# power_supply.net
KiCad netlist of a schematic drawn in Altium Designer
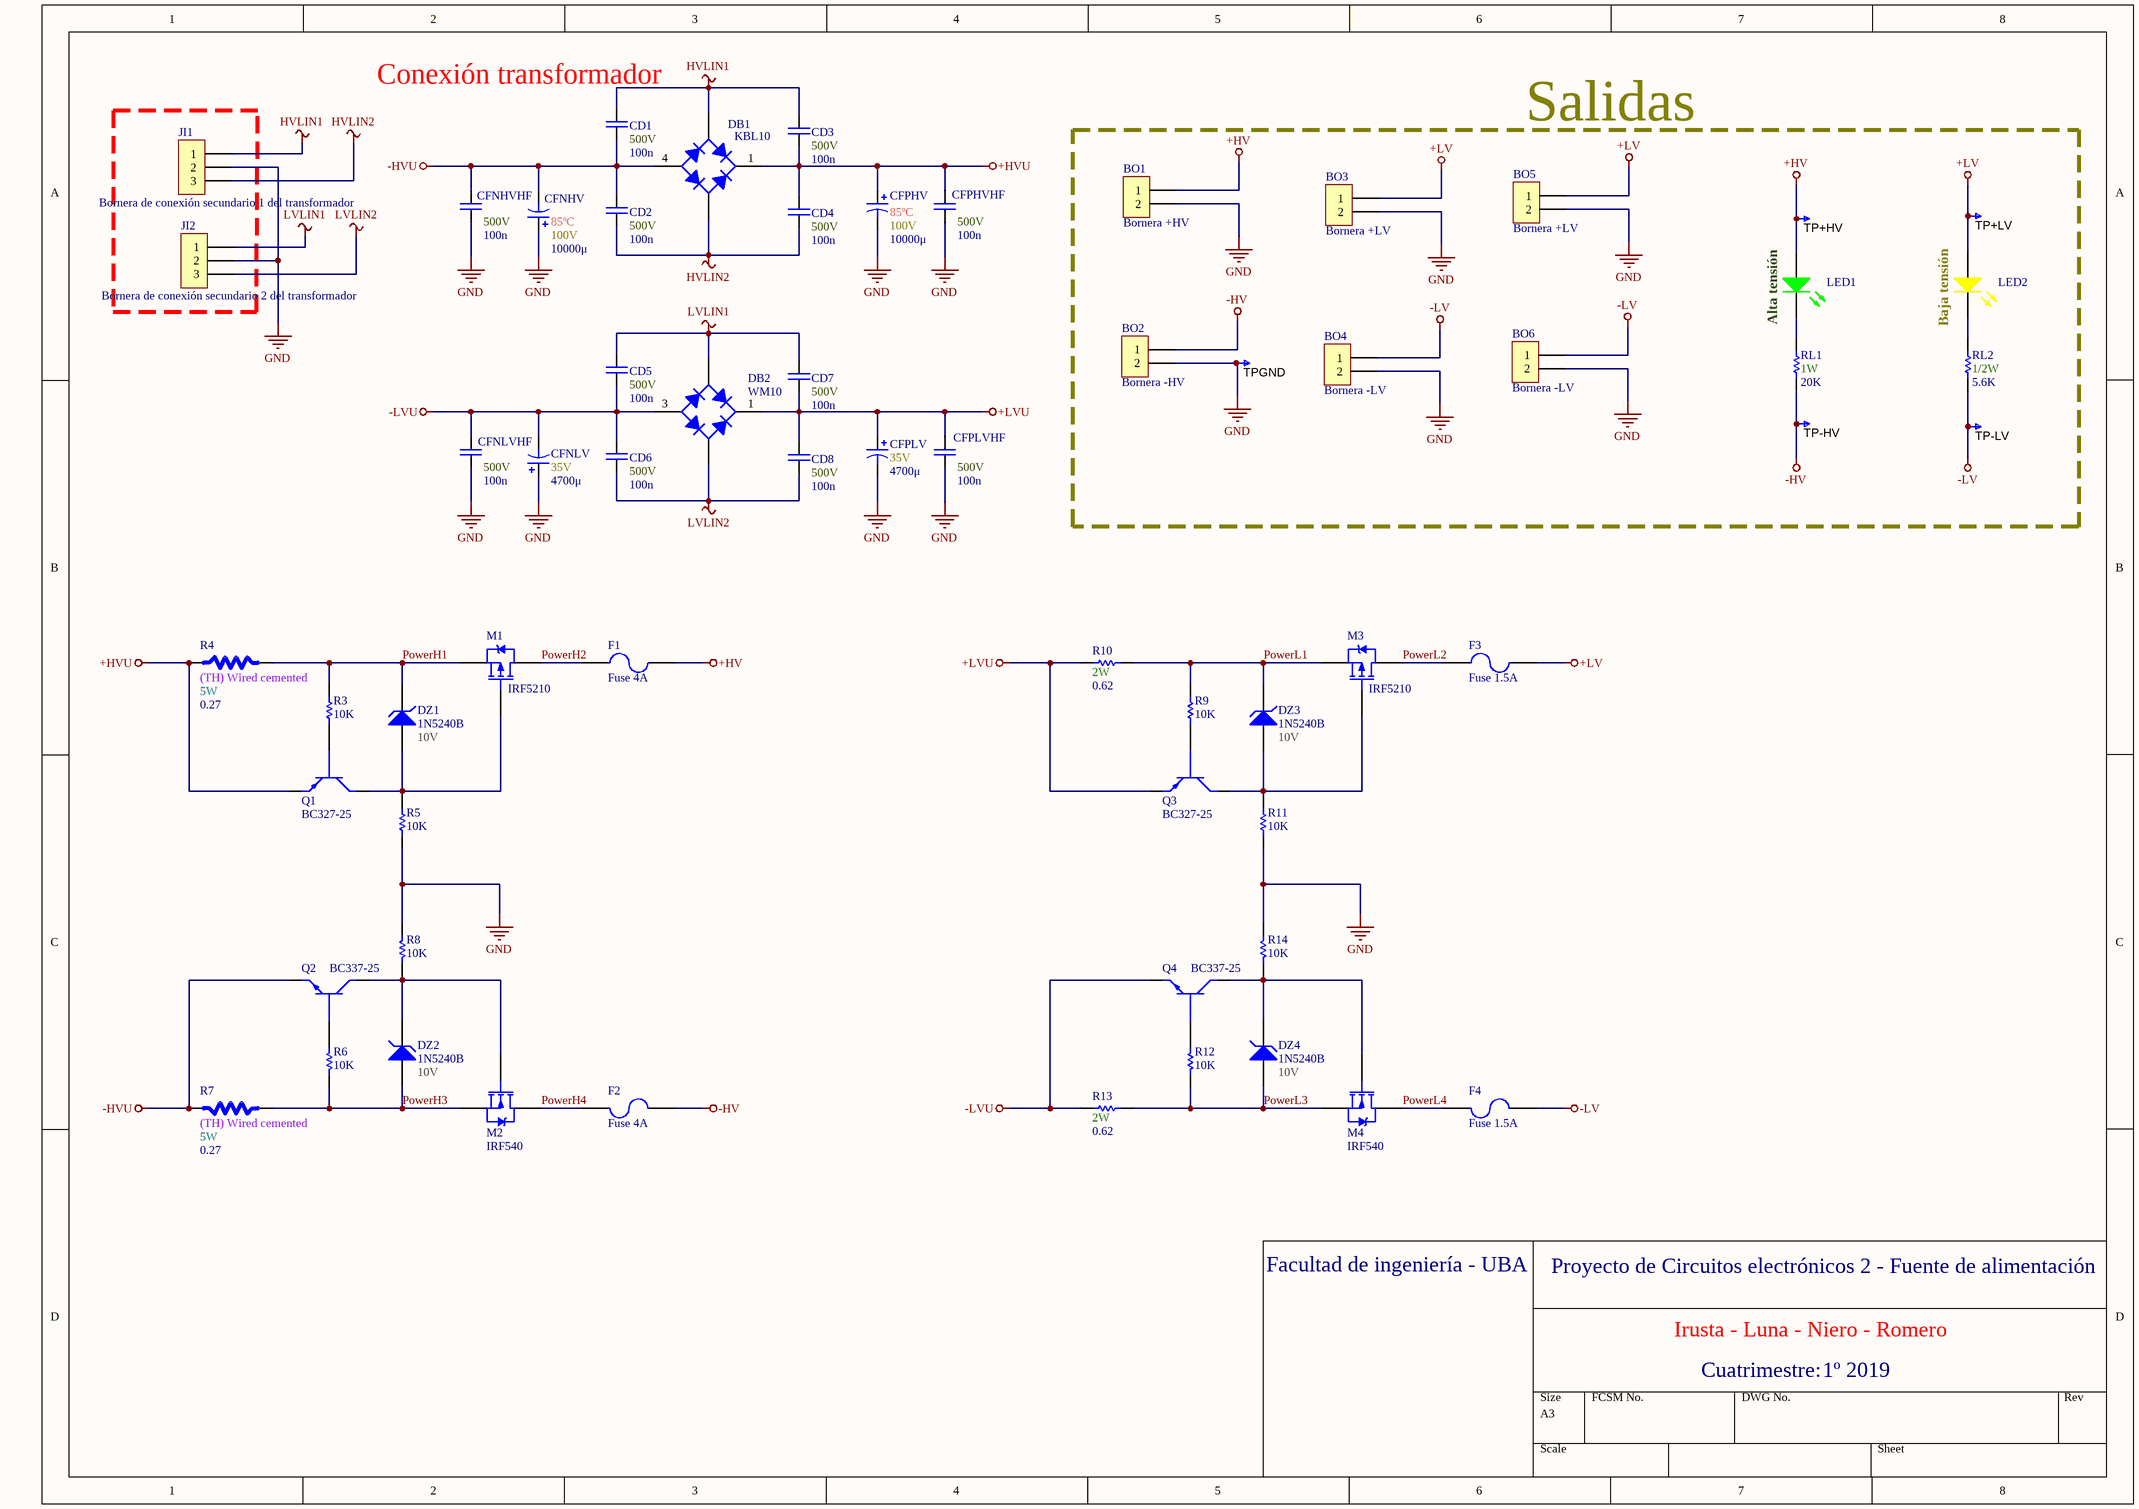
[diagram p0: power_supply.SchDoc]

(export (version "E")
  (design (tool "Eeschema 10.0.6"))
  (components
    (comp (ref "BO1")
      (value "Bornera +HV")
      (footprint "TE-C-282822-2-C-PLUGGED")
      (description "TERMI-BLOK HEADER,ASSY90 2P - serie 282822 - 5.00mm")
      (fields (field (name "MANUFACTURER") "TE Connectivity") (field (name "PARTNO") "C-282822-2-C"))
      (libsource (lib "Connectors") (part "C-282822-2-C"))
    )
    (comp (ref "BO2")
      (value "Bornera -HV")
      (footprint "TE-C-282822-2-C-PLUGGED")
      (description "TERMI-BLOK HEADER,ASSY90 2P - serie 282822 - 5.00mm")
      (fields (field (name "MANUFACTURER") "TE Connectivity") (field (name "PARTNO") "C-282822-2-C"))
      (libsource (lib "Connectors") (part "C-282822-2-C"))
    )
    (comp (ref "BO3")
      (value "Bornera +LV")
      (footprint "TE-C-282822-2-C-PLUGGED")
      (description "TERMI-BLOK HEADER,ASSY90 2P - serie 282822 - 5.00mm")
      (fields (field (name "MANUFACTURER") "TE Connectivity") (field (name "PARTNO") "C-282822-2-C"))
      (libsource (lib "Connectors") (part "C-282822-2-C"))
    )
    (comp (ref "BO4")
      (value "Bornera -LV")
      (footprint "TE-C-282822-2-C-PLUGGED")
      (description "TERMI-BLOK HEADER,ASSY90 2P - serie 282822 - 5.00mm")
      (fields (field (name "MANUFACTURER") "TE Connectivity") (field (name "PARTNO") "C-282822-2-C"))
      (libsource (lib "Connectors") (part "C-282822-2-C"))
    )
    (comp (ref "BO5")
      (value "Bornera +LV")
      (footprint "TE-C-282822-2-C-PLUGGED")
      (description "TERMI-BLOK HEADER,ASSY90 2P - serie 282822 - 5.00mm")
      (fields (field (name "MANUFACTURER") "TE Connectivity") (field (name "PARTNO") "C-282822-2-C"))
      (libsource (lib "Connectors") (part "C-282822-2-C"))
    )
    (comp (ref "BO6")
      (value "Bornera -LV")
      (footprint "TE-C-282822-2-C-PLUGGED")
      (description "TERMI-BLOK HEADER,ASSY90 2P - serie 282822 - 5.00mm")
      (fields (field (name "MANUFACTURER") "TE Connectivity") (field (name "PARTNO") "C-282822-2-C"))
      (libsource (lib "Connectors") (part "C-282822-2-C"))
    )
    (comp (ref "CD1")
      (value "100n")
      (footprint "Cer. pitch 5.0mm height 5.5mm")
      (description "Ceramic Capacitor 100nF 500V 10%")
      (fields
        (field (name "TOLERANCE") "10%")
        (field (name "VOLTAGE") "500V")
        (field (name "Comment") "Cer. 100n 500V 10%")
      )
      (libsource (lib "Capacitors") (part "Cer. 100n 500V 10%"))
    )
    (comp (ref "CD2")
      (value "100n")
      (footprint "Cer. pitch 5.0mm height 5.5mm")
      (description "Ceramic Capacitor 100nF 500V 10%")
      (fields
        (field (name "TOLERANCE") "10%")
        (field (name "VOLTAGE") "500V")
        (field (name "Comment") "Cer. 100n 500V 10%")
      )
      (libsource (lib "Capacitors") (part "Cer. 100n 500V 10%"))
    )
    (comp (ref "CD3")
      (value "100n")
      (footprint "Cer. pitch 5.0mm height 5.5mm")
      (description "Ceramic Capacitor 100nF 500V 10%")
      (fields
        (field (name "TOLERANCE") "10%")
        (field (name "VOLTAGE") "500V")
        (field (name "Comment") "Cer. 100n 500V 10%")
      )
      (libsource (lib "Capacitors") (part "Cer. 100n 500V 10%"))
    )
    (comp (ref "CD4")
      (value "100n")
      (footprint "Cer. pitch 5.0mm height 5.5mm")
      (description "Ceramic Capacitor 100nF 500V 10%")
      (fields
        (field (name "TOLERANCE") "10%")
        (field (name "VOLTAGE") "500V")
        (field (name "Comment") "Cer. 100n 500V 10%")
      )
      (libsource (lib "Capacitors") (part "Cer. 100n 500V 10%"))
    )
    (comp (ref "CD5")
      (value "100n")
      (footprint "Cer. pitch 5.0mm height 5.5mm")
      (description "Ceramic Capacitor 100nF 500V 10%")
      (fields
        (field (name "TOLERANCE") "10%")
        (field (name "VOLTAGE") "500V")
        (field (name "Comment") "Cer. 100n 500V 10%")
      )
      (libsource (lib "Capacitors") (part "Cer. 100n 500V 10%"))
    )
    (comp (ref "CD6")
      (value "100n")
      (footprint "Cer. pitch 5.0mm height 5.5mm")
      (description "Ceramic Capacitor 100nF 500V 10%")
      (fields
        (field (name "TOLERANCE") "10%")
        (field (name "VOLTAGE") "500V")
        (field (name "Comment") "Cer. 100n 500V 10%")
      )
      (libsource (lib "Capacitors") (part "Cer. 100n 500V 10%"))
    )
    (comp (ref "CD7")
      (value "100n")
      (footprint "Cer. pitch 5.0mm height 5.5mm")
      (description "Ceramic Capacitor 100nF 500V 10%")
      (fields
        (field (name "TOLERANCE") "10%")
        (field (name "VOLTAGE") "500V")
        (field (name "Comment") "Cer. 100n 500V 10%")
      )
      (libsource (lib "Capacitors") (part "Cer. 100n 500V 10%"))
    )
    (comp (ref "CD8")
      (value "100n")
      (footprint "Cer. pitch 5.0mm height 5.5mm")
      (description "Ceramic Capacitor 100nF 500V 10%")
      (fields
        (field (name "TOLERANCE") "10%")
        (field (name "VOLTAGE") "500V")
        (field (name "Comment") "Cer. 100n 500V 10%")
      )
      (libsource (lib "Capacitors") (part "Cer. 100n 500V 10%"))
    )
    (comp (ref "CFNHV")
      (value "10000μ")
      (footprint "Al. Electrolytic 35.0mmx50.0mmx10mm-CLEAN")
      (description "Aluminum Electrolytic Capacitor 10000μF 100V 20% 85º")
      (fields
        (field (name "TOLERANCE") "20%")
        (field (name "TEMPERATURE") "85ºC")
        (field (name "VOLTAGE") "100V")
        (field (name "Comment") "Al. Elect. 10000u 100V 20% 85º")
      )
      (libsource (lib "Capacitors") (part "Al. Elect. 10000u 100V 20% 85º"))
    )
    (comp (ref "CFNHVHF")
      (value "100n")
      (footprint "Cer. pitch 5.0mm height 5.5mm")
      (description "Ceramic Capacitor 100nF 500V 10%")
      (fields
        (field (name "TOLERANCE") "10%")
        (field (name "VOLTAGE") "500V")
        (field (name "Comment") "Cer. 100n 500V 10%")
      )
      (libsource (lib "Capacitors") (part "Cer. 100n 500V 10%"))
    )
    (comp (ref "CFNLV")
      (value "4700μ")
      (footprint "Al. Electrolytic 18.0mmx36.0mmx7.5mm")
      (description "Aluminum Electrolytic Capacitor 4700μF 35V 20%")
      (fields
        (field (name "TOLERANCE") "20%")
        (field (name "VOLTAGE") "35V")
        (field (name "Comment") "Al. Elect. 4700u 35V 20%")
      )
      (libsource (lib "Capacitors") (part "Al. Elect. 4700u 35V 20%"))
    )
    (comp (ref "CFNLVHF")
      (value "100n")
      (footprint "Cer. pitch 5.0mm height 5.5mm")
      (description "Ceramic Capacitor 100nF 500V 10%")
      (fields
        (field (name "TOLERANCE") "10%")
        (field (name "VOLTAGE") "500V")
        (field (name "Comment") "Cer. 100n 500V 10%")
      )
      (libsource (lib "Capacitors") (part "Cer. 100n 500V 10%"))
    )
    (comp (ref "CFPHV")
      (value "10000μ")
      (footprint "Al. Electrolytic 35.0mmx50.0mmx10mm-CLEAN")
      (description "Aluminum Electrolytic Capacitor 10000μF 100V 20% 85º")
      (fields
        (field (name "TOLERANCE") "20%")
        (field (name "TEMPERATURE") "85ºC")
        (field (name "VOLTAGE") "100V")
        (field (name "Comment") "Al. Elect. 10000u 100V 20% 85º")
      )
      (libsource (lib "") (part "Al. Elect. 10000u 100V 20% 85º_1"))
    )
    (comp (ref "CFPHVHF")
      (value "100n")
      (footprint "Cer. pitch 5.0mm height 5.5mm")
      (description "Ceramic Capacitor 100nF 500V 10%")
      (fields
        (field (name "TOLERANCE") "10%")
        (field (name "VOLTAGE") "500V")
        (field (name "Comment") "Cer. 100n 500V 10%")
      )
      (libsource (lib "Capacitors") (part "Cer. 100n 500V 10%"))
    )
    (comp (ref "CFPLV")
      (value "4700μ")
      (footprint "Al. Electrolytic 18.0mmx36.0mmx7.5mm")
      (description "Aluminum Electrolytic Capacitor 4700μF 35V 20%")
      (fields
        (field (name "TOLERANCE") "20%")
        (field (name "VOLTAGE") "35V")
        (field (name "Comment") "Al. Elect. 4700u 35V 20%")
      )
      (libsource (lib "Capacitors") (part "Al. Elect. 4700u 35V 20%"))
    )
    (comp (ref "CFPLVHF")
      (value "100n")
      (footprint "Cer. pitch 5.0mm height 5.5mm")
      (description "Ceramic Capacitor 100nF 500V 10%")
      (fields
        (field (name "TOLERANCE") "10%")
        (field (name "VOLTAGE") "500V")
        (field (name "Comment") "Cer. 100n 500V 10%")
      )
      (libsource (lib "Capacitors") (part "Cer. 100n 500V 10%"))
    )
    (comp (ref "DB1")
      (value "KBL10")
      (footprint "KBL")
      (description "Single phase silicon bridge rectifier 1000V 4A")
      (fields (field (name "VOLTAGE") "1000V"))
      (libsource (lib "diode-bridges") (part "KBL10"))
    )
    (comp (ref "DB2")
      (value "WM10")
      (footprint "WOM-4")
      (description "Single phase silicon bridge rectifier 1000V 1.5A")
      (fields (field (name "VOLTAGE") "1000V"))
      (libsource (lib "diode-bridges") (part "WM10"))
    )
    (comp (ref "DZ1")
      (value "1N5240B")
      (footprint "DO-35-0.3mil")
      (description "Zener Diode, 10V, 500mW")
      (fields
        (field (name "MANUFACTURER") "Microsemi")
        (field (name "POWER") "500mW")
        (field (name "ZV") "10V")
        (field (name "PUBLISHER") "Altium Limited")
      )
      (libsource (lib "MICROSEMI") (part "1N5240B"))
    )
    (comp (ref "DZ2")
      (value "1N5240B")
      (footprint "DO-35-0.3mil")
      (description "Zener Diode, 10V, 500mW")
      (fields
        (field (name "MANUFACTURER") "Microsemi")
        (field (name "POWER") "500mW")
        (field (name "ZV") "10V")
        (field (name "PUBLISHER") "Altium Limited")
      )
      (libsource (lib "MICROSEMI") (part "1N5240B"))
    )
    (comp (ref "DZ3")
      (value "1N5240B")
      (footprint "DO-35-0.3mil")
      (description "Zener Diode, 10V, 500mW")
      (fields
        (field (name "MANUFACTURER") "Microsemi")
        (field (name "POWER") "500mW")
        (field (name "ZV") "10V")
        (field (name "PUBLISHER") "Altium Limited")
      )
      (libsource (lib "MICROSEMI") (part "1N5240B"))
    )
    (comp (ref "DZ4")
      (value "1N5240B")
      (footprint "DO-35-0.3mil")
      (description "Zener Diode, 10V, 500mW")
      (fields
        (field (name "MANUFACTURER") "Microsemi")
        (field (name "POWER") "500mW")
        (field (name "ZV") "10V")
        (field (name "PUBLISHER") "Altium Limited")
      )
      (libsource (lib "MICROSEMI") (part "1N5240B"))
    )
    (comp (ref "F1")
      (value "Fuse 4A")
      (footprint "DINKLE FUSE HOLDER 5X20")
      (description "Fuse")
      (libsource (lib "") (part "Fuse Holder_1"))
    )
    (comp (ref "F2")
      (value "Fuse 4A")
      (footprint "DINKLE FUSE HOLDER 5X20")
      (description "Fuse")
      (libsource (lib "Fuses") (part "Fuse Holder"))
    )
    (comp (ref "F3")
      (value "Fuse 1.5A")
      (footprint "DINKLE FUSE HOLDER 5X20")
      (description "Fuse")
      (libsource (lib "") (part "Fuse Holder_1"))
    )
    (comp (ref "F4")
      (value "Fuse 1.5A")
      (footprint "DINKLE FUSE HOLDER 5X20")
      (description "Fuse")
      (libsource (lib "Fuses") (part "Fuse Holder"))
    )
    (comp (ref "JI1")
      (value "Bornera de conexión secundario 1 del transformador")
      (footprint "TE-C-282822-3-C-PLUGGED")
      (description "TERMI-BLOK HEADER,ASSY90 3P - serie 282822 - 5.00mm")
      (fields (field (name "MANUFACTURER") "TE Connectivity") (field (name "PARTNO") "C-282822-3-C"))
      (libsource (lib "Connectors") (part "C-282822-3-C"))
    )
    (comp (ref "JI2")
      (value "Bornera de conexión secundario 2 del transformador")
      (footprint "TE-C-282822-3-C-PLUGGED")
      (description "TERMI-BLOK HEADER,ASSY90 3P - serie 282822 - 5.00mm")
      (fields (field (name "MANUFACTURER") "TE Connectivity") (field (name "PARTNO") "C-282822-3-C"))
      (libsource (lib "Connectors") (part "C-282822-3-C"))
    )
    (comp (ref "LED1")
      (value "Alta tensión")
      (footprint "LED_5MM_GREEN")
      (description "Typical LED (GREEN)")
      (fields (field (name "PUBLISHER") "Altium Limited"))
      (libsource (lib "GENERIC_LED") (part "LED (GREEN)"))
    )
    (comp (ref "LED2")
      (value "Baja tensión")
      (footprint "LED_5MM_YELLOW")
      (description "Typical LED (YELLOW)")
      (fields (field (name "PUBLISHER") "Altium Limited"))
      (libsource (lib "GENERIC_LED") (part "LED (YELLOW)"))
    )
    (comp (ref "M1")
      (value "IRF5210")
      (footprint "TO-220-FULL")
      (description "P-CHANNEL Power MOSFET 100V - 40A -  0.06Ω")
      (fields
        (field (name "POWER") "200W")
        (field (name "COPYRIGHT") "Copyright (C) 2015 Accelerated Designs. All rights reserved")
      )
      (libsource (lib "New IR Discrete MOSFET - Power") (part "IRF5210"))
    )
    (comp (ref "M2")
      (value "IRF540")
      (footprint "TO-220-FULL")
      (description "N-CHANNEL Power MOSFET 100V - 20A -  0.077Ω")
      (fields
        (field (name "POWER") "150")
        (field (name "COPYRIGHT") "Copyright (C) 2015 Accelerated Designs. All rights reserved")
      )
      (libsource (lib "VISHAY Discrete MOSFET - Power") (part "IRF540"))
    )
    (comp (ref "M3")
      (value "IRF5210")
      (footprint "TO-220-FULL")
      (description "P-CHANNEL Power MOSFET 100V - 40A -  0.06Ω")
      (fields
        (field (name "POWER") "200W")
        (field (name "COPYRIGHT") "Copyright (C) 2015 Accelerated Designs. All rights reserved")
      )
      (libsource (lib "New IR Discrete MOSFET - Power") (part "IRF5210"))
    )
    (comp (ref "M4")
      (value "IRF540")
      (footprint "TO-220-FULL")
      (description "N-CHANNEL Power MOSFET 100V - 20A -  0.077Ω")
      (fields
        (field (name "POWER") "150")
        (field (name "COPYRIGHT") "Copyright (C) 2015 Accelerated Designs. All rights reserved")
      )
      (libsource (lib "VISHAY Discrete MOSFET - Power") (part "IRF540"))
    )
    (comp (ref "Q1")
      (value "BC327-25")
      (footprint "TO-92-1")
      (description "PNP Bipolar Transistor")
      (fields (field (name "MANUFACTURER") "ON Semiconductor") (field (name "PARTNUMBER") "MJE340G"))
      (libsource (lib "ON Semi Transistors") (part "BC327-25"))
    )
    (comp (ref "Q2")
      (value "BC337-25")
      (footprint "TO-92-1")
      (description "NPN Bipolar Transistor")
      (fields (field (name "MANUFACTURER") "ON Semiconductor") (field (name "PARTNUMBER") "MJE340G"))
      (libsource (lib "ON Semi Transistors") (part "BC337-25"))
    )
    (comp (ref "Q3")
      (value "BC327-25")
      (footprint "TO-92-1")
      (description "PNP Bipolar Transistor")
      (fields (field (name "MANUFACTURER") "ON Semiconductor") (field (name "PARTNUMBER") "MJE340G"))
      (libsource (lib "ON Semi Transistors") (part "BC327-25"))
    )
    (comp (ref "Q4")
      (value "BC337-25")
      (footprint "TO-92-1")
      (description "NPN Bipolar Transistor")
      (fields (field (name "MANUFACTURER") "ON Semiconductor") (field (name "PARTNUMBER") "MJE340G"))
      (libsource (lib "ON Semi Transistors") (part "BC337-25"))
    )
    (comp (ref "R3")
      (value "10K")
      (footprint "AXIAL-0.4-E24-0_25W-10k")
      (description "Resistor 10KΩ 1/4W 5%")
      (fields (field (name "POWER") "1/4W") (field (name "TOLERANCE") "5%"))
      (libsource (lib "Resistors") (part "Resistor 10K 1/4W 5%"))
    )
    (comp (ref "R4")
      (value "0.27")
      (footprint "Cemented resistor 0.27 5W 5%")
      (description "Cemented resistor 0.27Ω 5% 5W")
      (fields
        (field (name "TOLERANCE") "5%")
        (field (name "TYPE") "(TH) Wired cemented")
        (field (name "POWER") "5W")
        (field (name "Comment") "Cemented resistor 0.27 5W 5%")
      )
      (libsource (lib "Resistors") (part "Cemented resistor 0.27 5W 5%"))
    )
    (comp (ref "R5")
      (value "10K")
      (footprint "AXIAL-0.4-E24-0_25W-10k")
      (description "Resistor 10KΩ 1/4W 5%")
      (fields (field (name "POWER") "1/4W") (field (name "TOLERANCE") "5%"))
      (libsource (lib "Resistors") (part "Resistor 10K 1/4W 5%"))
    )
    (comp (ref "R6")
      (value "10K")
      (footprint "AXIAL-0.4-E24-0_25W-10k")
      (description "Resistor 10KΩ 1/4W 5%")
      (fields (field (name "POWER") "1/4W") (field (name "TOLERANCE") "5%"))
      (libsource (lib "Resistors") (part "Resistor 10K 1/4W 5%"))
    )
    (comp (ref "R7")
      (value "0.27")
      (footprint "Cemented resistor 0.27 5W 5%")
      (description "Cemented resistor 0.27Ω 5% 5W")
      (fields
        (field (name "TOLERANCE") "5%")
        (field (name "TYPE") "(TH) Wired cemented")
        (field (name "POWER") "5W")
        (field (name "Comment") "Cemented resistor 0.27 5W 5%")
      )
      (libsource (lib "Resistors") (part "Cemented resistor 0.27 5W 5%"))
    )
    (comp (ref "R8")
      (value "10K")
      (footprint "AXIAL-0.4-E24-0_25W-10k")
      (description "Resistor 10KΩ 1/4W 5%")
      (fields (field (name "POWER") "1/4W") (field (name "TOLERANCE") "5%"))
      (libsource (lib "Resistors") (part "Resistor 10K 1/4W 5%"))
    )
    (comp (ref "R9")
      (value "10K")
      (footprint "AXIAL-0.4-E24-0_25W-10k")
      (description "Resistor 10KΩ 1/4W 5%")
      (fields (field (name "POWER") "1/4W") (field (name "TOLERANCE") "5%"))
      (libsource (lib "Resistors") (part "Resistor 10K 1/4W 5%"))
    )
    (comp (ref "R10")
      (value "0.62")
      (footprint "AXIAL-0.6-E24-2W-0.62")
      (description "Resistor 0.62Ω 2W 5%")
      (fields
        (field (name "TOLERANCE") "5%")
        (field (name "POWER") "2W")
        (field (name "Comment") "Resistor 0.62 2W 5%")
      )
      (libsource (lib "Resistors") (part "Resistor 0.62 2W 5%"))
    )
    (comp (ref "R11")
      (value "10K")
      (footprint "AXIAL-0.4-E24-0_25W-10k")
      (description "Resistor 10KΩ 1/4W 5%")
      (fields (field (name "POWER") "1/4W") (field (name "TOLERANCE") "5%"))
      (libsource (lib "Resistors") (part "Resistor 10K 1/4W 5%"))
    )
    (comp (ref "R12")
      (value "10K")
      (footprint "AXIAL-0.4-E24-0_25W-10k")
      (description "Resistor 10KΩ 1/4W 5%")
      (fields (field (name "POWER") "1/4W") (field (name "TOLERANCE") "5%"))
      (libsource (lib "Resistors") (part "Resistor 10K 1/4W 5%"))
    )
    (comp (ref "R13")
      (value "0.62")
      (footprint "AXIAL-0.6-E24-2W-0.62")
      (description "Resistor 0.62Ω 2W 5%")
      (fields
        (field (name "TOLERANCE") "5%")
        (field (name "POWER") "2W")
        (field (name "Comment") "Resistor 0.62 2W 5%")
      )
      (libsource (lib "Resistors") (part "Resistor 0.62 2W 5%"))
    )
    (comp (ref "R14")
      (value "10K")
      (footprint "AXIAL-0.4-E24-0_25W-10k")
      (description "Resistor 10KΩ 1/4W 5%")
      (fields (field (name "POWER") "1/4W") (field (name "TOLERANCE") "5%"))
      (libsource (lib "Resistors") (part "Resistor 10K 1/4W 5%"))
    )
    (comp (ref "RL1")
      (value "20K")
      (footprint "AXIAL-0.6-E24-1W-20K")
      (description "Resistor 20KΩ 1W 5%")
      (fields
        (field (name "TOLERANCE") "5%")
        (field (name "POWER") "1W")
        (field (name "Comment") "Resistor 20K 1W 5%")
      )
      (libsource (lib "Resistors") (part "Resistor 20K 1W 5%"))
    )
    (comp (ref "RL2")
      (value "5.6K")
      (footprint "AXIAL-0.5-E24-0_5W-5.6K")
      (description "Resistor 5.6KΩ 1/2W 5%")
      (fields
        (field (name "TOLERANCE") "5%")
        (field (name "POWER") "1/2W")
        (field (name "Comment") "Resistor 5.6K 1/2W 5%")
      )
      (libsource (lib "Resistors") (part "Resistor 5.6K 1/2W 5%"))
    )
    (comp (ref "TP+HV")
      (value "TESTPOINT_THT")
      (footprint "TP-THT-MULTI")
      (description "Test Point PCB mount Multi-purpose Black")
      (fields (field (name "PBL PART NUMBER") "3100-xxx"))
      (libsource (lib "Test Points and Jumpers") (part "TESTPOINT_THT"))
    )
    (comp (ref "TP+LV")
      (value "TESTPOINT_THT")
      (footprint "TP-THT-MULTI")
      (description "Test Point PCB mount Multi-purpose Black")
      (fields (field (name "PBL PART NUMBER") "3100-xxx"))
      (libsource (lib "Test Points and Jumpers") (part "TESTPOINT_THT"))
    )
    (comp (ref "TP-HV")
      (value "TESTPOINT_THT")
      (footprint "TP-THT-MULTI")
      (description "Test Point PCB mount Multi-purpose Black")
      (fields (field (name "PBL PART NUMBER") "3100-xxx"))
      (libsource (lib "Test Points and Jumpers") (part "TESTPOINT_THT"))
    )
    (comp (ref "TP-LV")
      (value "TESTPOINT_THT")
      (footprint "TP-THT-MULTI")
      (description "Test Point PCB mount Multi-purpose Black")
      (fields (field (name "PBL PART NUMBER") "3100-xxx"))
      (libsource (lib "Test Points and Jumpers") (part "TESTPOINT_THT"))
    )
    (comp (ref "TPGND")
      (value "TESTPOINT_THT")
      (footprint "TP-THT-MULTI")
      (description "Test Point PCB mount Multi-purpose Black")
      (fields (field (name "PBL PART NUMBER") "3100-xxx"))
      (libsource (lib "Test Points and Jumpers") (part "TESTPOINT_THT"))
    )
  )
  (nets
    (net (code "1") (name "+HV") (class "Default")
      (node (ref "BO1") (pin "1") (pinfunction "1_1") (pintype "power_in"))
      (node (ref "F1") (pin "1") (pinfunction "1_1") (pintype "passive"))
      (node (ref "LED1") (pin "A") (pinfunction "A_A") (pintype "passive"))
      (node (ref "TP+HV") (pin "1") (pintype "passive"))
    )
    (net (code "2") (name "+HVU") (class "Default")
      (node (ref "CD3") (pin "1") (pinfunction "1_1") (pintype "passive"))
      (node (ref "CD4") (pin "2") (pinfunction "2_2") (pintype "passive"))
      (node (ref "CFPHV") (pin "1") (pinfunction "1_1") (pintype "passive"))
      (node (ref "CFPHVHF") (pin "2") (pinfunction "2_2") (pintype "passive"))
      (node (ref "DB1") (pin "1") (pinfunction "V+_1") (pintype "passive"))
      (node (ref "Q1") (pin "3") (pinfunction "E_3") (pintype "passive"))
      (node (ref "R4") (pin "1") (pinfunction "1_1") (pintype "passive"))
    )
    (net (code "3") (name "+LV") (class "Default")
      (node (ref "BO3") (pin "1") (pinfunction "1_1") (pintype "power_in"))
      (node (ref "BO5") (pin "1") (pinfunction "1_1") (pintype "power_in"))
      (node (ref "F3") (pin "1") (pinfunction "1_1") (pintype "passive"))
      (node (ref "LED2") (pin "A") (pinfunction "A_A") (pintype "passive"))
      (node (ref "TP+LV") (pin "1") (pintype "passive"))
    )
    (net (code "4") (name "+LVU") (class "Default")
      (node (ref "CD7") (pin "1") (pinfunction "1_1") (pintype "passive"))
      (node (ref "CD8") (pin "2") (pinfunction "2_2") (pintype "passive"))
      (node (ref "CFPLV") (pin "1") (pinfunction "1_1") (pintype "passive"))
      (node (ref "CFPLVHF") (pin "2") (pinfunction "2_2") (pintype "passive"))
      (node (ref "DB2") (pin "1") (pinfunction "V+_1") (pintype "passive"))
      (node (ref "Q3") (pin "3") (pinfunction "E_3") (pintype "passive"))
      (node (ref "R10") (pin "1") (pinfunction "1_1") (pintype "passive"))
    )
    (net (code "5") (name "-HV") (class "Default")
      (node (ref "BO2") (pin "1") (pinfunction "1_1") (pintype "power_in"))
      (node (ref "F2") (pin "1") (pinfunction "1_1") (pintype "passive"))
      (node (ref "RL1") (pin "1") (pinfunction "1_1") (pintype "passive"))
      (node (ref "TP-HV") (pin "1") (pintype "passive"))
    )
    (net (code "6") (name "-HVU") (class "Default")
      (node (ref "CD1") (pin "1") (pinfunction "1_1") (pintype "passive"))
      (node (ref "CD2") (pin "2") (pinfunction "2_2") (pintype "passive"))
      (node (ref "CFNHV") (pin "2") (pinfunction "2_2") (pintype "passive"))
      (node (ref "CFNHVHF") (pin "2") (pinfunction "2_2") (pintype "passive"))
      (node (ref "DB1") (pin "4") (pinfunction "V-_4") (pintype "passive"))
      (node (ref "Q2") (pin "3") (pinfunction "E_3") (pintype "passive"))
      (node (ref "R7") (pin "1") (pinfunction "1_1") (pintype "passive"))
    )
    (net (code "7") (name "-LV") (class "Default")
      (node (ref "BO4") (pin "1") (pinfunction "1_1") (pintype "power_in"))
      (node (ref "BO6") (pin "1") (pinfunction "1_1") (pintype "power_in"))
      (node (ref "F4") (pin "1") (pinfunction "1_1") (pintype "passive"))
      (node (ref "RL2") (pin "1") (pinfunction "1_1") (pintype "passive"))
      (node (ref "TP-LV") (pin "1") (pintype "passive"))
    )
    (net (code "8") (name "-LVU") (class "Default")
      (node (ref "CD5") (pin "1") (pinfunction "1_1") (pintype "passive"))
      (node (ref "CD6") (pin "2") (pinfunction "2_2") (pintype "passive"))
      (node (ref "CFNLV") (pin "2") (pinfunction "2_2") (pintype "passive"))
      (node (ref "CFNLVHF") (pin "2") (pinfunction "2_2") (pintype "passive"))
      (node (ref "DB2") (pin "3") (pinfunction "V-_3") (pintype "passive"))
      (node (ref "Q4") (pin "3") (pinfunction "E_3") (pintype "passive"))
      (node (ref "R13") (pin "1") (pinfunction "1_1") (pintype "passive"))
    )
    (net (code "9") (name "/PowerH1") (class "Default")
      (node (ref "DZ1") (pin "2") (pinfunction "K_2") (pintype "passive"))
      (node (ref "M1") (pin "3") (pinfunction "S_3") (pintype "passive"))
      (node (ref "R3") (pin "2") (pinfunction "2_2") (pintype "passive"))
      (node (ref "R4") (pin "2") (pinfunction "2_2") (pintype "passive"))
    )
    (net (code "10") (name "/PowerH2") (class "Default")
      (node (ref "F1") (pin "2") (pinfunction "2_2") (pintype "passive"))
      (node (ref "M1") (pin "2") (pinfunction "D_2") (pintype "passive"))
    )
    (net (code "11") (name "/PowerH3") (class "Default")
      (node (ref "DZ2") (pin "1") (pinfunction "A_1") (pintype "passive"))
      (node (ref "M2") (pin "3") (pinfunction "S_3") (pintype "passive"))
      (node (ref "R6") (pin "2") (pinfunction "2_2") (pintype "passive"))
      (node (ref "R7") (pin "2") (pinfunction "2_2") (pintype "passive"))
    )
    (net (code "12") (name "/PowerH4") (class "Default")
      (node (ref "F2") (pin "2") (pinfunction "2_2") (pintype "passive"))
      (node (ref "M2") (pin "2") (pinfunction "D_2") (pintype "passive"))
    )
    (net (code "13") (name "/PowerL1") (class "Default")
      (node (ref "DZ3") (pin "2") (pinfunction "K_2") (pintype "passive"))
      (node (ref "M3") (pin "3") (pinfunction "S_3") (pintype "passive"))
      (node (ref "R10") (pin "2") (pinfunction "2_2") (pintype "passive"))
      (node (ref "R9") (pin "2") (pinfunction "2_2") (pintype "passive"))
    )
    (net (code "14") (name "/PowerL2") (class "Default")
      (node (ref "F3") (pin "2") (pinfunction "2_2") (pintype "passive"))
      (node (ref "M3") (pin "2") (pinfunction "D_2") (pintype "passive"))
    )
    (net (code "15") (name "/PowerL3") (class "Default")
      (node (ref "DZ4") (pin "1") (pinfunction "A_1") (pintype "passive"))
      (node (ref "M4") (pin "3") (pinfunction "S_3") (pintype "passive"))
      (node (ref "R12") (pin "2") (pinfunction "2_2") (pintype "passive"))
      (node (ref "R13") (pin "2") (pinfunction "2_2") (pintype "passive"))
    )
    (net (code "16") (name "/PowerL4") (class "Default")
      (node (ref "F4") (pin "2") (pinfunction "2_2") (pintype "passive"))
      (node (ref "M4") (pin "2") (pinfunction "D_2") (pintype "passive"))
    )
    (net (code "17") (name "GND") (class "Default")
      (node (ref "BO1") (pin "2") (pinfunction "2_2") (pintype "passive"))
      (node (ref "BO2") (pin "2") (pinfunction "2_2") (pintype "passive"))
      (node (ref "BO3") (pin "2") (pinfunction "2_2") (pintype "passive"))
      (node (ref "BO4") (pin "2") (pinfunction "2_2") (pintype "passive"))
      (node (ref "BO5") (pin "2") (pinfunction "2_2") (pintype "passive"))
      (node (ref "BO6") (pin "2") (pinfunction "2_2") (pintype "passive"))
      (node (ref "CFNHV") (pin "1") (pinfunction "1_1") (pintype "passive"))
      (node (ref "CFNHVHF") (pin "1") (pinfunction "1_1") (pintype "passive"))
      (node (ref "CFNLV") (pin "1") (pinfunction "1_1") (pintype "passive"))
      (node (ref "CFNLVHF") (pin "1") (pinfunction "1_1") (pintype "passive"))
      (node (ref "CFPHV") (pin "2") (pinfunction "2_2") (pintype "passive"))
      (node (ref "CFPHVHF") (pin "1") (pinfunction "1_1") (pintype "passive"))
      (node (ref "CFPLV") (pin "2") (pinfunction "2_2") (pintype "passive"))
      (node (ref "CFPLVHF") (pin "1") (pinfunction "1_1") (pintype "passive"))
      (node (ref "JI1") (pin "2") (pinfunction "2_2") (pintype "passive"))
      (node (ref "JI2") (pin "2") (pinfunction "2_2") (pintype "passive"))
      (node (ref "R11") (pin "1") (pinfunction "1_1") (pintype "passive"))
      (node (ref "R14") (pin "1") (pinfunction "1_1") (pintype "passive"))
      (node (ref "R5") (pin "1") (pinfunction "1_1") (pintype "passive"))
      (node (ref "R8") (pin "1") (pinfunction "1_1") (pintype "passive"))
      (node (ref "TPGND") (pin "1") (pintype "passive"))
    )
    (net (code "18") (name "HVLIN1") (class "Default")
      (node (ref "CD1") (pin "2") (pinfunction "2_2") (pintype "passive"))
      (node (ref "CD3") (pin "2") (pinfunction "2_2") (pintype "passive"))
      (node (ref "DB1") (pin "2") (pinfunction "AC1_2") (pintype "passive"))
      (node (ref "JI1") (pin "1") (pinfunction "1_1") (pintype "passive"))
    )
    (net (code "19") (name "HVLIN2") (class "Default")
      (node (ref "CD2") (pin "1") (pinfunction "1_1") (pintype "passive"))
      (node (ref "CD4") (pin "1") (pinfunction "1_1") (pintype "passive"))
      (node (ref "DB1") (pin "3") (pinfunction "AC2_3") (pintype "passive"))
      (node (ref "JI1") (pin "3") (pinfunction "3_3") (pintype "passive"))
    )
    (net (code "20") (name "LVLIN1") (class "Default")
      (node (ref "CD5") (pin "2") (pinfunction "2_2") (pintype "passive"))
      (node (ref "CD7") (pin "2") (pinfunction "2_2") (pintype "passive"))
      (node (ref "DB2") (pin "4") (pinfunction "AC2_4") (pintype "passive"))
      (node (ref "JI2") (pin "1") (pinfunction "1_1") (pintype "passive"))
    )
    (net (code "21") (name "LVLIN2") (class "Default")
      (node (ref "CD6") (pin "1") (pinfunction "1_1") (pintype "passive"))
      (node (ref "CD8") (pin "1") (pinfunction "1_1") (pintype "passive"))
      (node (ref "DB2") (pin "2") (pinfunction "AC1_2") (pintype "passive"))
      (node (ref "JI2") (pin "3") (pinfunction "3_3") (pintype "passive"))
    )
    (net (code "22") (name "Net-(DZ1-A)") (class "Default")
      (node (ref "DZ1") (pin "1") (pinfunction "A_1") (pintype "passive"))
      (node (ref "M1") (pin "1") (pinfunction "G_1") (pintype "passive"))
      (node (ref "Q1") (pin "1") (pinfunction "C_1") (pintype "passive"))
      (node (ref "R5") (pin "2") (pinfunction "2_2") (pintype "passive"))
    )
    (net (code "23") (name "Net-(DZ2-K)") (class "Default")
      (node (ref "DZ2") (pin "2") (pinfunction "K_2") (pintype "passive"))
      (node (ref "M2") (pin "1") (pinfunction "G_1") (pintype "passive"))
      (node (ref "Q2") (pin "1") (pinfunction "C_1") (pintype "passive"))
      (node (ref "R8") (pin "2") (pinfunction "2_2") (pintype "passive"))
    )
    (net (code "24") (name "Net-(DZ3-A)") (class "Default")
      (node (ref "DZ3") (pin "1") (pinfunction "A_1") (pintype "passive"))
      (node (ref "M3") (pin "1") (pinfunction "G_1") (pintype "passive"))
      (node (ref "Q3") (pin "1") (pinfunction "C_1") (pintype "passive"))
      (node (ref "R11") (pin "2") (pinfunction "2_2") (pintype "passive"))
    )
    (net (code "25") (name "Net-(DZ4-K)") (class "Default")
      (node (ref "DZ4") (pin "2") (pinfunction "K_2") (pintype "passive"))
      (node (ref "M4") (pin "1") (pinfunction "G_1") (pintype "passive"))
      (node (ref "Q4") (pin "1") (pinfunction "C_1") (pintype "passive"))
      (node (ref "R14") (pin "2") (pinfunction "2_2") (pintype "passive"))
    )
    (net (code "26") (name "Net-(LED1-PadK)") (class "Default")
      (node (ref "LED1") (pin "K") (pinfunction "K_K") (pintype "passive"))
      (node (ref "RL1") (pin "2") (pinfunction "2_2") (pintype "passive"))
    )
    (net (code "27") (name "Net-(LED2-PadK)") (class "Default")
      (node (ref "LED2") (pin "K") (pinfunction "K_K") (pintype "passive"))
      (node (ref "RL2") (pin "2") (pinfunction "2_2") (pintype "passive"))
    )
    (net (code "28") (name "Net-(Q1-B)") (class "Default")
      (node (ref "Q1") (pin "2") (pinfunction "B_2") (pintype "passive"))
      (node (ref "R3") (pin "1") (pinfunction "1_1") (pintype "passive"))
    )
    (net (code "29") (name "Net-(Q2-B)") (class "Default")
      (node (ref "Q2") (pin "2") (pinfunction "B_2") (pintype "passive"))
      (node (ref "R6") (pin "1") (pinfunction "1_1") (pintype "passive"))
    )
    (net (code "30") (name "Net-(Q3-B)") (class "Default")
      (node (ref "Q3") (pin "2") (pinfunction "B_2") (pintype "passive"))
      (node (ref "R9") (pin "1") (pinfunction "1_1") (pintype "passive"))
    )
    (net (code "31") (name "Net-(Q4-B)") (class "Default")
      (node (ref "Q4") (pin "2") (pinfunction "B_2") (pintype "passive"))
      (node (ref "R12") (pin "1") (pinfunction "1_1") (pintype "passive"))
    )
  )
)
